# Modules2_v3.net
KiCad netlist of a schematic drawn in Altium Designer
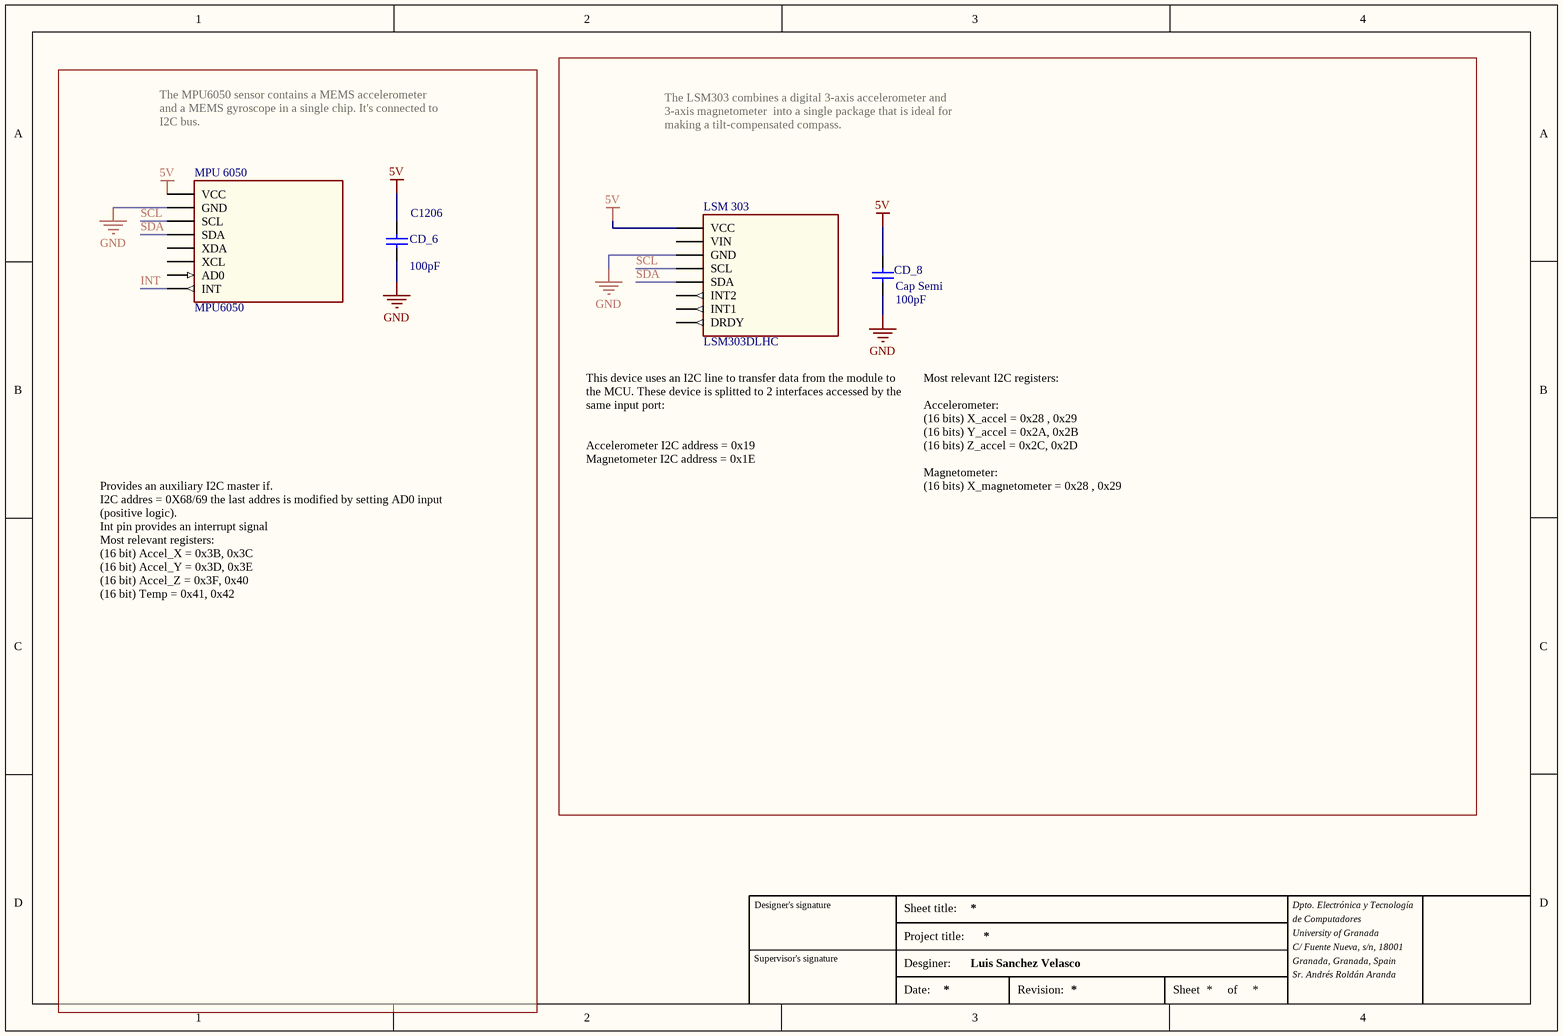
[diagram p0: Modules2_v3.SchDoc]

(export (version "E")
  (design (tool "Eeschema 10.0.6"))
  (components
    (comp (ref "CD_6")
      (value "100pF")
      (footprint "C1206")
      (description "Capacitor (Semiconductor SIM Model)")
      (fields
        (field (name "PACKAGEREFERENCE") "C1206")
        (field (name "Comment") "Cap Semi")
        (field (name "PUBLISHER") "Altium Limited")
      )
      (libsource (lib "Miscellaneous Devices") (part "Cap Semi"))
    )
    (comp (ref "CD_8")
      (value "Cap Semi")
      (footprint "C1206")
      (description "Capacitor (Semiconductor SIM Model)")
      (fields (field (name "ALTIUM_VALUE") "100pF") (field (name "PUBLISHER") "Altium Limited"))
      (libsource (lib "Miscellaneous Devices") (part "Cap Semi"))
    )
    (comp (ref "LSM 303")
      (value "LSM303DLHC")
      (footprint "1X08 - LSM303")
      (description "Header, 8-Pin")
      (fields (field (name "PUBLISHER") "Altium Limited"))
      (libsource (lib "Trackuino_Shield") (part "LSMsimple"))
    )
    (comp (ref "MPU 6050")
      (value "MPU6050")
      (footprint "1X08 - MPU6050")
      (description "Header, 8-Pin")
      (fields (field (name "PUBLISHER") "Altium Limited"))
      (libsource (lib "Trackuino_Shield") (part "MPUsimple"))
    )
  )
  (nets
    (net (code "1") (name "/INT") (class "Default")
      (node (ref "MPU 6050") (pin "INT") (pinfunction "INT_INT") (pintype "output"))
    )
    (net (code "2") (name "/SCL") (class "Default")
      (node (ref "LSM 303") (pin "SCL") (pinfunction "SCL_SCL") (pintype "open_collector"))
      (node (ref "MPU 6050") (pin "SCL") (pinfunction "SCL_SCL") (pintype "open_collector"))
    )
    (net (code "3") (name "/SDA") (class "Default")
      (node (ref "LSM 303") (pin "SDA") (pinfunction "SDA_SDA") (pintype "open_collector"))
      (node (ref "MPU 6050") (pin "SDA") (pinfunction "SDA_SDA") (pintype "open_collector"))
    )
    (net (code "4") (name "5V") (class "Default")
      (node (ref "CD_6") (pin "2") (pinfunction "2_2") (pintype "passive"))
      (node (ref "CD_8") (pin "2") (pinfunction "2_2") (pintype "passive"))
      (node (ref "LSM 303") (pin "VCC") (pinfunction "VCC_VCC") (pintype "power_in"))
      (node (ref "MPU 6050") (pin "VCC") (pinfunction "VCC_VCC") (pintype "power_in"))
    )
    (net (code "5") (name "GND") (class "Default")
      (node (ref "CD_6") (pin "1") (pinfunction "1_1") (pintype "passive"))
      (node (ref "CD_8") (pin "1") (pinfunction "1_1") (pintype "passive"))
      (node (ref "LSM 303") (pin "GND") (pinfunction "GND_GND") (pintype "power_in"))
      (node (ref "MPU 6050") (pin "GND") (pinfunction "GND_GND") (pintype "power_in"))
    )
    (net (code "6") (name "unconnected-(LSM 303-PadDRDY)") (class "Default")
      (node (ref "LSM 303") (pin "DRDY") (pinfunction "DRDY_DRDY") (pintype "output"))
    )
    (net (code "7") (name "unconnected-(LSM 303-PadINT1)") (class "Default")
      (node (ref "LSM 303") (pin "INT1") (pinfunction "INT1_INT1") (pintype "output"))
    )
    (net (code "8") (name "unconnected-(LSM 303-PadINT2)") (class "Default")
      (node (ref "LSM 303") (pin "INT2") (pinfunction "INT2_INT2") (pintype "output"))
    )
    (net (code "9") (name "unconnected-(LSM 303-PadVIN)") (class "Default")
      (node (ref "LSM 303") (pin "VIN") (pinfunction "VIN_VIN") (pintype "power_in"))
    )
    (net (code "10") (name "unconnected-(MPU 6050-PadAD0)") (class "Default")
      (node (ref "MPU 6050") (pin "AD0") (pinfunction "AD0_AD0") (pintype "input"))
    )
    (net (code "11") (name "unconnected-(MPU 6050-PadXCL)") (class "Default")
      (node (ref "MPU 6050") (pin "XCL") (pinfunction "XCL_XCL") (pintype "open_collector"))
    )
    (net (code "12") (name "unconnected-(MPU 6050-PadXDA)") (class "Default")
      (node (ref "MPU 6050") (pin "XDA") (pinfunction "XDA_XDA") (pintype "open_collector"))
    )
  )
)
